# MCU.net
KiCad netlist of a schematic drawn in Altium Designer
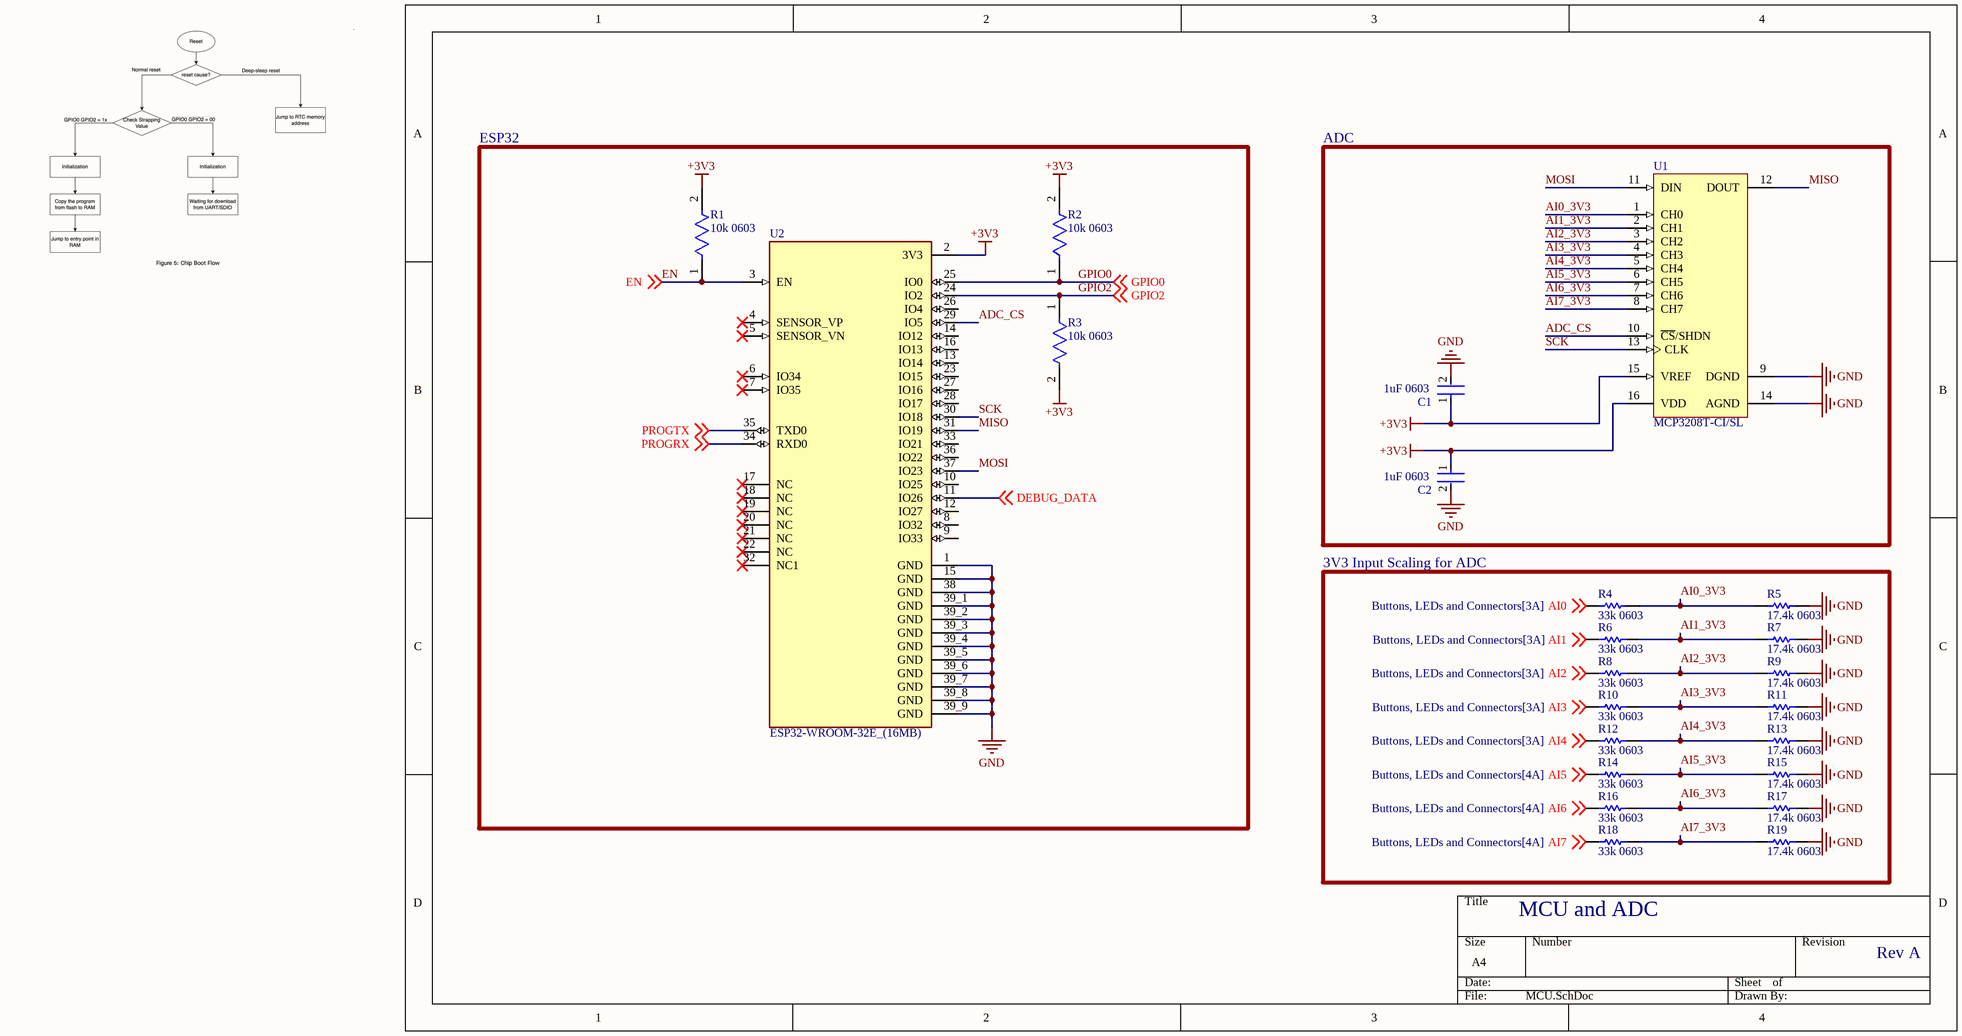
[diagram p0: MCU.SchDoc]

(export (version "E")
  (design (tool "Eeschema 10.0.6"))
  (components
    (comp (ref "C1")
      (value "1uF 0603")
      (footprint "FP-CC0603-DA-MFG")
      (description "CAP CER 1UF 25V X5R 0603")
      (fields
        (field (name "OCTOPART") "https://octopart.com/cc0603krx5r8bb105-yageo-9292811")
        (field (name "MANUFACTURER") "YAGEO")
      )
      (libsource (lib "Altium Content Vault") (part "11868f565c42a9108669ba33697ecf6"))
    )
    (comp (ref "C2")
      (value "1uF 0603")
      (footprint "FP-CC0603-DA-MFG")
      (description "CAP CER 1UF 25V X5R 0603")
      (fields
        (field (name "OCTOPART") "https://octopart.com/cc0603krx5r8bb105-yageo-9292811")
        (field (name "MANUFACTURER") "YAGEO")
      )
      (libsource (lib "Altium Content Vault") (part "11868f565c42a9108669ba33697ecf6"))
    )
    (comp (ref "R1")
      (value "10k 0603")
      (footprint "FP-RC0603-0_55-IPC_C")
      (description "RES 10K OHM 1% 1/10W 0603")
      (fields (field (name "TOLERANCE") "1%"))
      (libsource (lib "Altium Content Vault") (part "1029c3af85768c4190bb7ad29bc67b5"))
    )
    (comp (ref "R2")
      (value "10k 0603")
      (footprint "FP-RC0603-0_55-IPC_C")
      (description "RES 10K OHM 1% 1/10W 0603")
      (fields (field (name "TOLERANCE") "1%"))
      (libsource (lib "Altium Content Vault") (part "1029c3af85768c4190bb7ad29bc67b5"))
    )
    (comp (ref "R3")
      (value "10k 0603")
      (footprint "FP-RC0603-0_55-IPC_C")
      (description "RES 10K OHM 1% 1/10W 0603")
      (fields (field (name "TOLERANCE") "1%"))
      (libsource (lib "Altium Content Vault") (part "1029c3af85768c4190bb7ad29bc67b5"))
    )
    (comp (ref "R4")
      (value "33k 0603")
      (footprint "RESC1608X55X25LL10T15")
      (description "Chip Resistor, 33 Ohm, +/- 1%, 0.1 W, -55 to 155 degC, 0603 (1608 Metric), RoHS, Tape and Reel")
      (fields (field (name "TOLERANCE") "1%") (field (name "MANUFACTURER") "Yageo"))
      (libsource (lib "Altium Content Vault") (part "RES-2"))
    )
    (comp (ref "R5")
      (value "17.4k 0603")
      (footprint "RESC1608X55X25NL10T15")
      (fields (field (name "PART NUMBER") "RC0603FR-0717K4L") (field (name "MANUFACTURER") "Yageo"))
      (libsource (lib "Altium Content Vault") (part "RES"))
    )
    (comp (ref "R6")
      (value "33k 0603")
      (footprint "RESC1608X55X25LL10T15")
      (description "Chip Resistor, 33 Ohm, +/- 1%, 0.1 W, -55 to 155 degC, 0603 (1608 Metric), RoHS, Tape and Reel")
      (fields (field (name "TOLERANCE") "1%") (field (name "MANUFACTURER") "Yageo"))
      (libsource (lib "Altium Content Vault") (part "RES-2"))
    )
    (comp (ref "R7")
      (value "17.4k 0603")
      (footprint "RESC1608X55X25NL10T15")
      (fields (field (name "PART NUMBER") "RC0603FR-0717K4L") (field (name "MANUFACTURER") "Yageo"))
      (libsource (lib "Altium Content Vault") (part "RES"))
    )
    (comp (ref "R8")
      (value "33k 0603")
      (footprint "RESC1608X55X25LL10T15")
      (description "Chip Resistor, 33 Ohm, +/- 1%, 0.1 W, -55 to 155 degC, 0603 (1608 Metric), RoHS, Tape and Reel")
      (fields (field (name "TOLERANCE") "1%") (field (name "MANUFACTURER") "Yageo"))
      (libsource (lib "Altium Content Vault") (part "RES-2"))
    )
    (comp (ref "R9")
      (value "17.4k 0603")
      (footprint "RESC1608X55X25NL10T15")
      (fields (field (name "PART NUMBER") "RC0603FR-0717K4L") (field (name "MANUFACTURER") "Yageo"))
      (libsource (lib "Altium Content Vault") (part "RES"))
    )
    (comp (ref "R10")
      (value "33k 0603")
      (footprint "RESC1608X55X25LL10T15")
      (description "Chip Resistor, 33 Ohm, +/- 1%, 0.1 W, -55 to 155 degC, 0603 (1608 Metric), RoHS, Tape and Reel")
      (fields (field (name "TOLERANCE") "1%") (field (name "MANUFACTURER") "Yageo"))
      (libsource (lib "Altium Content Vault") (part "RES-2"))
    )
    (comp (ref "R11")
      (value "17.4k 0603")
      (footprint "RESC1608X55X25NL10T15")
      (fields (field (name "PART NUMBER") "RC0603FR-0717K4L") (field (name "MANUFACTURER") "Yageo"))
      (libsource (lib "Altium Content Vault") (part "RES"))
    )
    (comp (ref "R12")
      (value "33k 0603")
      (footprint "RESC1608X55X25LL10T15")
      (description "Chip Resistor, 33 Ohm, +/- 1%, 0.1 W, -55 to 155 degC, 0603 (1608 Metric), RoHS, Tape and Reel")
      (fields (field (name "TOLERANCE") "1%") (field (name "MANUFACTURER") "Yageo"))
      (libsource (lib "Altium Content Vault") (part "RES-2"))
    )
    (comp (ref "R13")
      (value "17.4k 0603")
      (footprint "RESC1608X55X25NL10T15")
      (fields (field (name "PART NUMBER") "RC0603FR-0717K4L") (field (name "MANUFACTURER") "Yageo"))
      (libsource (lib "Altium Content Vault") (part "RES"))
    )
    (comp (ref "R14")
      (value "33k 0603")
      (footprint "RESC1608X55X25LL10T15")
      (description "Chip Resistor, 33 Ohm, +/- 1%, 0.1 W, -55 to 155 degC, 0603 (1608 Metric), RoHS, Tape and Reel")
      (fields (field (name "TOLERANCE") "1%") (field (name "MANUFACTURER") "Yageo"))
      (libsource (lib "Altium Content Vault") (part "RES-2"))
    )
    (comp (ref "R15")
      (value "17.4k 0603")
      (footprint "RESC1608X55X25NL10T15")
      (fields (field (name "PART NUMBER") "RC0603FR-0717K4L") (field (name "MANUFACTURER") "Yageo"))
      (libsource (lib "Altium Content Vault") (part "RES"))
    )
    (comp (ref "R16")
      (value "33k 0603")
      (footprint "RESC1608X55X25LL10T15")
      (description "Chip Resistor, 33 Ohm, +/- 1%, 0.1 W, -55 to 155 degC, 0603 (1608 Metric), RoHS, Tape and Reel")
      (fields (field (name "TOLERANCE") "1%") (field (name "MANUFACTURER") "Yageo"))
      (libsource (lib "Altium Content Vault") (part "RES-2"))
    )
    (comp (ref "R17")
      (value "17.4k 0603")
      (footprint "RESC1608X55X25NL10T15")
      (fields (field (name "PART NUMBER") "RC0603FR-0717K4L") (field (name "MANUFACTURER") "Yageo"))
      (libsource (lib "Altium Content Vault") (part "RES"))
    )
    (comp (ref "R18")
      (value "33k 0603")
      (footprint "RESC1608X55X25LL10T15")
      (description "Chip Resistor, 33 Ohm, +/- 1%, 0.1 W, -55 to 155 degC, 0603 (1608 Metric), RoHS, Tape and Reel")
      (fields (field (name "TOLERANCE") "1%") (field (name "MANUFACTURER") "Yageo"))
      (libsource (lib "Altium Content Vault") (part "RES-2"))
    )
    (comp (ref "R19")
      (value "17.4k 0603")
      (footprint "RESC1608X55X25NL10T15")
      (fields (field (name "PART NUMBER") "RC0603FR-0717K4L") (field (name "MANUFACTURER") "Yageo"))
      (libsource (lib "Altium Content Vault") (part "RES"))
    )
    (comp (ref "U1")
      (value "MCP3208T-CI/SL")
      (footprint "SOIC-SL16_L")
      (libsource (lib "Altium Content Vault") (part "CON-ADC-MCP3008-16"))
    )
    (comp (ref "U2")
      (value "ESP32-WROOM-32E_(16MB)")
      (footprint "ESP32-WROOM-32E (16MB):XCVR_ESP32-WROOM-32E_(16MB)")
      (fields (field (name "MF") "{'manufacturer': u'Espressif Systems'}"))
      (libsource (lib "*") (part "ESP32-WROOM-32E_(16MB)"))
    )
  )
  (nets
    (net (code "1") (name "+3V3") (class "Default")
      (node (ref "C1") (pin "1") (pinfunction "1_1") (pintype "passive"))
      (node (ref "C2") (pin "1") (pinfunction "1_1") (pintype "passive"))
      (node (ref "R1") (pin "2") (pinfunction "2_2") (pintype "passive"))
      (node (ref "R2") (pin "2") (pinfunction "2_2") (pintype "passive"))
      (node (ref "R3") (pin "2") (pinfunction "2_2") (pintype "passive"))
      (node (ref "U1") (pin "15") (pinfunction "VREF_15") (pintype "input"))
      (node (ref "U1") (pin "16") (pinfunction "VDD_16") (pintype "power_in"))
      (node (ref "U2") (pin "2") (pinfunction "3V3_2") (pintype "power_in"))
    )
    (net (code "2") (name "/ADC_CS") (class "Default")
      (node (ref "U1") (pin "10") (pinfunction "~{CS}/SHDN_10") (pintype "input"))
      (node (ref "U2") (pin "29") (pinfunction "IO5_29") (pintype "bidirectional"))
    )
    (net (code "3") (name "/AI0_3V3") (class "Default")
      (node (ref "R4") (pin "2") (pinfunction "2_2") (pintype "passive"))
      (node (ref "R5") (pin "2") (pinfunction "2_2") (pintype "passive"))
      (node (ref "U1") (pin "1") (pinfunction "CH0_1") (pintype "input"))
    )
    (net (code "4") (name "/AI1_3V3") (class "Default")
      (node (ref "R6") (pin "2") (pinfunction "2_2") (pintype "passive"))
      (node (ref "R7") (pin "2") (pinfunction "2_2") (pintype "passive"))
      (node (ref "U1") (pin "2") (pinfunction "CH1_2") (pintype "input"))
    )
    (net (code "5") (name "/AI2_3V3") (class "Default")
      (node (ref "R8") (pin "2") (pinfunction "2_2") (pintype "passive"))
      (node (ref "R9") (pin "2") (pinfunction "2_2") (pintype "passive"))
      (node (ref "U1") (pin "3") (pinfunction "CH2_3") (pintype "input"))
    )
    (net (code "6") (name "/AI3_3V3") (class "Default")
      (node (ref "R10") (pin "2") (pinfunction "2_2") (pintype "passive"))
      (node (ref "R11") (pin "2") (pinfunction "2_2") (pintype "passive"))
      (node (ref "U1") (pin "4") (pinfunction "CH3_4") (pintype "input"))
    )
    (net (code "7") (name "/AI4_3V3") (class "Default")
      (node (ref "R12") (pin "2") (pinfunction "2_2") (pintype "passive"))
      (node (ref "R13") (pin "2") (pinfunction "2_2") (pintype "passive"))
      (node (ref "U1") (pin "5") (pinfunction "CH4_5") (pintype "input"))
    )
    (net (code "8") (name "/AI5_3V3") (class "Default")
      (node (ref "R14") (pin "2") (pinfunction "2_2") (pintype "passive"))
      (node (ref "R15") (pin "2") (pinfunction "2_2") (pintype "passive"))
      (node (ref "U1") (pin "6") (pinfunction "CH5_6") (pintype "input"))
    )
    (net (code "9") (name "/AI6_3V3") (class "Default")
      (node (ref "R16") (pin "2") (pinfunction "2_2") (pintype "passive"))
      (node (ref "R17") (pin "2") (pinfunction "2_2") (pintype "passive"))
      (node (ref "U1") (pin "7") (pinfunction "CH6_7") (pintype "input"))
    )
    (net (code "10") (name "/AI7_3V3") (class "Default")
      (node (ref "R18") (pin "2") (pinfunction "2_2") (pintype "passive"))
      (node (ref "R19") (pin "2") (pinfunction "2_2") (pintype "passive"))
      (node (ref "U1") (pin "8") (pinfunction "CH7_8") (pintype "input"))
    )
    (net (code "11") (name "/MISO") (class "Default")
      (node (ref "U1") (pin "12") (pinfunction "DOUT_12") (pintype "tri_state"))
      (node (ref "U2") (pin "31") (pinfunction "IO19_31") (pintype "bidirectional"))
    )
    (net (code "12") (name "/MOSI") (class "Default")
      (node (ref "U1") (pin "11") (pinfunction "DIN_11") (pintype "input"))
      (node (ref "U2") (pin "37") (pinfunction "IO23_37") (pintype "bidirectional"))
    )
    (net (code "13") (name "/SCK") (class "Default")
      (node (ref "U1") (pin "13") (pinfunction "CLK_13") (pintype "input"))
      (node (ref "U2") (pin "30") (pinfunction "IO18_30") (pintype "bidirectional"))
    )
    (net (code "14") (name "AI0") (class "Default")
      (node (ref "R4") (pin "1") (pinfunction "1_1") (pintype "passive"))
    )
    (net (code "15") (name "AI1") (class "Default")
      (node (ref "R6") (pin "1") (pinfunction "1_1") (pintype "passive"))
    )
    (net (code "16") (name "AI2") (class "Default")
      (node (ref "R8") (pin "1") (pinfunction "1_1") (pintype "passive"))
    )
    (net (code "17") (name "AI3") (class "Default")
      (node (ref "R10") (pin "1") (pinfunction "1_1") (pintype "passive"))
    )
    (net (code "18") (name "AI4") (class "Default")
      (node (ref "R12") (pin "1") (pinfunction "1_1") (pintype "passive"))
    )
    (net (code "19") (name "AI5") (class "Default")
      (node (ref "R14") (pin "1") (pinfunction "1_1") (pintype "passive"))
    )
    (net (code "20") (name "AI6") (class "Default")
      (node (ref "R16") (pin "1") (pinfunction "1_1") (pintype "passive"))
    )
    (net (code "21") (name "AI7") (class "Default")
      (node (ref "R18") (pin "1") (pinfunction "1_1") (pintype "passive"))
    )
    (net (code "22") (name "DEBUG_DATA") (class "Default")
      (node (ref "U2") (pin "11") (pinfunction "IO26_11") (pintype "bidirectional"))
    )
    (net (code "23") (name "EN") (class "Default")
      (node (ref "R1") (pin "1") (pinfunction "1_1") (pintype "passive"))
      (node (ref "U2") (pin "3") (pinfunction "EN_3") (pintype "input"))
    )
    (net (code "24") (name "GND") (class "Default")
      (node (ref "C1") (pin "2") (pinfunction "2_2") (pintype "passive"))
      (node (ref "C2") (pin "2") (pinfunction "2_2") (pintype "passive"))
      (node (ref "R11") (pin "1") (pinfunction "1_1") (pintype "passive"))
      (node (ref "R13") (pin "1") (pinfunction "1_1") (pintype "passive"))
      (node (ref "R15") (pin "1") (pinfunction "1_1") (pintype "passive"))
      (node (ref "R17") (pin "1") (pinfunction "1_1") (pintype "passive"))
      (node (ref "R19") (pin "1") (pinfunction "1_1") (pintype "passive"))
      (node (ref "R5") (pin "1") (pinfunction "1_1") (pintype "passive"))
      (node (ref "R7") (pin "1") (pinfunction "1_1") (pintype "passive"))
      (node (ref "R9") (pin "1") (pinfunction "1_1") (pintype "passive"))
      (node (ref "U1") (pin "14") (pinfunction "AGND_14") (pintype "power_in"))
      (node (ref "U1") (pin "9") (pinfunction "DGND_9") (pintype "power_in"))
      (node (ref "U2") (pin "1") (pinfunction "GND_1") (pintype "power_in"))
      (node (ref "U2") (pin "15") (pinfunction "GND_15") (pintype "power_in"))
      (node (ref "U2") (pin "38") (pinfunction "GND_38") (pintype "power_in"))
      (node (ref "U2") (pin "39_1") (pinfunction "GND_39_1") (pintype "power_in"))
      (node (ref "U2") (pin "39_2") (pinfunction "GND_39_2") (pintype "power_in"))
      (node (ref "U2") (pin "39_3") (pinfunction "GND_39_3") (pintype "power_in"))
      (node (ref "U2") (pin "39_4") (pinfunction "GND_39_4") (pintype "power_in"))
      (node (ref "U2") (pin "39_5") (pinfunction "GND_39_5") (pintype "power_in"))
      (node (ref "U2") (pin "39_6") (pinfunction "GND_39_6") (pintype "power_in"))
      (node (ref "U2") (pin "39_7") (pinfunction "GND_39_7") (pintype "power_in"))
      (node (ref "U2") (pin "39_8") (pinfunction "GND_39_8") (pintype "power_in"))
      (node (ref "U2") (pin "39_9") (pinfunction "GND_39_9") (pintype "power_in"))
    )
    (net (code "25") (name "GPIO0") (class "Default")
      (node (ref "R2") (pin "1") (pinfunction "1_1") (pintype "passive"))
      (node (ref "U2") (pin "25") (pinfunction "IO0_25") (pintype "bidirectional"))
    )
    (net (code "26") (name "GPIO2") (class "Default")
      (node (ref "R3") (pin "1") (pinfunction "1_1") (pintype "passive"))
      (node (ref "U2") (pin "24") (pinfunction "IO2_24") (pintype "bidirectional"))
    )
    (net (code "27") (name "PROGRX") (class "Default")
      (node (ref "U2") (pin "34") (pinfunction "RXD0_34") (pintype "bidirectional"))
    )
    (net (code "28") (name "PROGTX") (class "Default")
      (node (ref "U2") (pin "35") (pinfunction "TXD0_35") (pintype "bidirectional"))
    )
    (net (code "29") (name "unconnected-(U2-IO4-Pad26)") (class "Default")
      (node (ref "U2") (pin "26") (pinfunction "IO4_26") (pintype "bidirectional"))
    )
    (net (code "30") (name "unconnected-(U2-IO12-Pad14)") (class "Default")
      (node (ref "U2") (pin "14") (pinfunction "IO12_14") (pintype "bidirectional"))
    )
    (net (code "31") (name "unconnected-(U2-IO13-Pad16)") (class "Default")
      (node (ref "U2") (pin "16") (pinfunction "IO13_16") (pintype "bidirectional"))
    )
    (net (code "32") (name "unconnected-(U2-IO14-Pad13)") (class "Default")
      (node (ref "U2") (pin "13") (pinfunction "IO14_13") (pintype "bidirectional"))
    )
    (net (code "33") (name "unconnected-(U2-IO15-Pad23)") (class "Default")
      (node (ref "U2") (pin "23") (pinfunction "IO15_23") (pintype "bidirectional"))
    )
    (net (code "34") (name "unconnected-(U2-IO16-Pad27)") (class "Default")
      (node (ref "U2") (pin "27") (pinfunction "IO16_27") (pintype "bidirectional"))
    )
    (net (code "35") (name "unconnected-(U2-IO17-Pad28)") (class "Default")
      (node (ref "U2") (pin "28") (pinfunction "IO17_28") (pintype "bidirectional"))
    )
    (net (code "36") (name "unconnected-(U2-IO21-Pad33)") (class "Default")
      (node (ref "U2") (pin "33") (pinfunction "IO21_33") (pintype "bidirectional"))
    )
    (net (code "37") (name "unconnected-(U2-IO22-Pad36)") (class "Default")
      (node (ref "U2") (pin "36") (pinfunction "IO22_36") (pintype "bidirectional"))
    )
    (net (code "38") (name "unconnected-(U2-IO25-Pad10)") (class "Default")
      (node (ref "U2") (pin "10") (pinfunction "IO25_10") (pintype "bidirectional"))
    )
    (net (code "39") (name "unconnected-(U2-IO27-Pad12)") (class "Default")
      (node (ref "U2") (pin "12") (pinfunction "IO27_12") (pintype "bidirectional"))
    )
    (net (code "40") (name "unconnected-(U2-IO32-Pad8)") (class "Default")
      (node (ref "U2") (pin "8") (pinfunction "IO32_8") (pintype "bidirectional"))
    )
    (net (code "41") (name "unconnected-(U2-IO33-Pad9)") (class "Default")
      (node (ref "U2") (pin "9") (pinfunction "IO33_9") (pintype "bidirectional"))
    )
    (net (code "42") (name "unconnected-(U2-IO34-Pad6)") (class "Default")
      (node (ref "U2") (pin "6") (pinfunction "IO34_6") (pintype "input+no_connect"))
    )
    (net (code "43") (name "unconnected-(U2-IO35-Pad7)") (class "Default")
      (node (ref "U2") (pin "7") (pinfunction "IO35_7") (pintype "input+no_connect"))
    )
    (net (code "44") (name "unconnected-(U2-NC-Pad17)") (class "Default")
      (node (ref "U2") (pin "17") (pinfunction "NC_17") (pintype "passive+no_connect"))
    )
    (net (code "45") (name "unconnected-(U2-NC-Pad18)") (class "Default")
      (node (ref "U2") (pin "18") (pinfunction "NC_18") (pintype "passive+no_connect"))
    )
    (net (code "46") (name "unconnected-(U2-NC-Pad19)") (class "Default")
      (node (ref "U2") (pin "19") (pinfunction "NC_19") (pintype "passive+no_connect"))
    )
    (net (code "47") (name "unconnected-(U2-NC-Pad20)") (class "Default")
      (node (ref "U2") (pin "20") (pinfunction "NC_20") (pintype "passive+no_connect"))
    )
    (net (code "48") (name "unconnected-(U2-NC-Pad21)") (class "Default")
      (node (ref "U2") (pin "21") (pinfunction "NC_21") (pintype "passive+no_connect"))
    )
    (net (code "49") (name "unconnected-(U2-NC-Pad22)") (class "Default")
      (node (ref "U2") (pin "22") (pinfunction "NC_22") (pintype "passive+no_connect"))
    )
    (net (code "50") (name "unconnected-(U2-NC1-Pad32)") (class "Default")
      (node (ref "U2") (pin "32") (pinfunction "NC1_32") (pintype "passive+no_connect"))
    )
    (net (code "51") (name "unconnected-(U2-SENSOR_VN-Pad5)") (class "Default")
      (node (ref "U2") (pin "5") (pinfunction "SENSOR_VN_5") (pintype "input+no_connect"))
    )
    (net (code "52") (name "unconnected-(U2-SENSOR_VP-Pad4)") (class "Default")
      (node (ref "U2") (pin "4") (pinfunction "SENSOR_VP_4") (pintype "input+no_connect"))
    )
  )
)
